# Main.net
KiCad netlist of a schematic drawn in Altium Designer
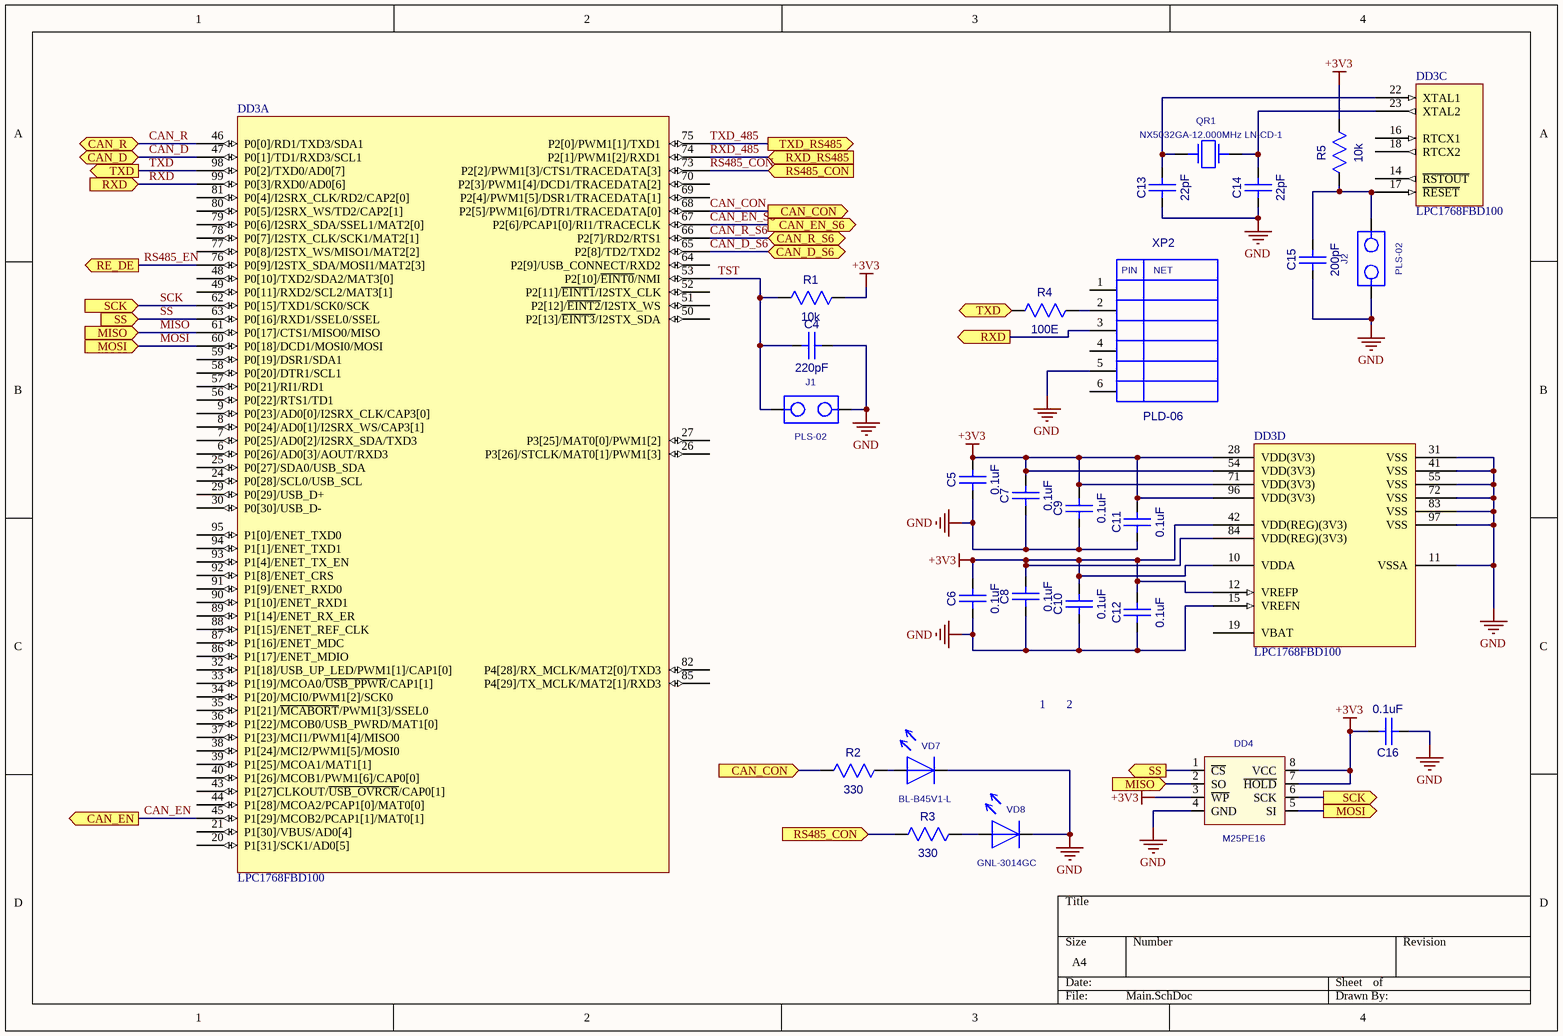
[diagram p0: Main.SchDoc]

(export (version "E")
  (design (tool "Eeschema 10.0.6"))
  (components
    (comp (ref "1")
      (value "REPER1.2")
      (footprint "REPER1.2")
      (libsource (lib "gprs_modem") (part "REPER1.2"))
    )
    (comp (ref "2")
      (value "REPER1.2")
      (footprint "REPER1.2")
      (libsource (lib "gprs_modem") (part "REPER1.2"))
    )
    (comp (ref "C4")
      (value "220pF")
      (footprint "CC0603-3M")
      (description "CC0603")
      (libsource (lib "gprs_modem") (part "CC0603"))
    )
    (comp (ref "C5")
      (value "0.1uF")
      (footprint "CC0603-3M")
      (description "CC0603")
      (libsource (lib "gprs_modem") (part "CC0603"))
    )
    (comp (ref "C6")
      (value "0.1uF")
      (footprint "CC0603-3M")
      (description "CC0603")
      (libsource (lib "gprs_modem") (part "CC0603"))
    )
    (comp (ref "C7")
      (value "0.1uF")
      (footprint "CC0603-3M")
      (description "CC0603")
      (libsource (lib "gprs_modem") (part "CC0603"))
    )
    (comp (ref "C8")
      (value "0.1uF")
      (footprint "CC0603-3M")
      (description "CC0603")
      (libsource (lib "gprs_modem") (part "CC0603"))
    )
    (comp (ref "C9")
      (value "0.1uF")
      (footprint "CC0603-3M")
      (description "CC0603")
      (libsource (lib "gprs_modem") (part "CC0603"))
    )
    (comp (ref "C10")
      (value "0.1uF")
      (footprint "CC0603-3M")
      (description "CC0603")
      (libsource (lib "gprs_modem") (part "CC0603"))
    )
    (comp (ref "C11")
      (value "0.1uF")
      (footprint "CC0603-3M")
      (description "CC0603")
      (libsource (lib "gprs_modem") (part "CC0603"))
    )
    (comp (ref "C12")
      (value "0.1uF")
      (footprint "CC0603-3M")
      (description "CC0603")
      (libsource (lib "gprs_modem") (part "CC0603"))
    )
    (comp (ref "C13")
      (value "22pF")
      (footprint "CC0603-3M")
      (description "CC0603")
      (libsource (lib "gprs_modem") (part "CC0603"))
    )
    (comp (ref "C14")
      (value "22pF")
      (footprint "CC0603-3M")
      (description "CC0603")
      (libsource (lib "gprs_modem") (part "CC0603"))
    )
    (comp (ref "C15")
      (value "200pF")
      (footprint "CC0603-3M")
      (description "CC0603")
      (libsource (lib "gprs_modem") (part "CC0603"))
    )
    (comp (ref "C16")
      (value "0.1uF")
      (footprint "CC0603-3M")
      (description "CC0603")
      (libsource (lib "") (part "CC0603_1"))
    )
    (comp (ref "DD3")
      (value "LPC1768FBD100")
      (footprint "TQFP-100")
      (description "Cortex -M3 32-Bit Microcontroller, 512KB Flash, 64KB RAM, 100-Lead LQFP")
      (libsource (lib "gprs_modem") (part "LPC1768FBD100"))
    )
    (comp (ref "DD4")
      (value "M25PE16")
      (footprint "EIAJ_SO8")
      (description "S25FL016A0LMFI01")
      (libsource (lib "gprs_modem") (part "S25FL016A0LMFI01"))
    )
    (comp (ref "J1") (value "PLS-02") (footprint "PLS-02") (libsource (lib "gprs_modem") (part "PLS-02")))
    (comp (ref "J2") (value "PLS-02") (footprint "PIN2W") (libsource (lib "gprs_modem") (part "PLS-02")))
    (comp (ref "QR1")
      (value "NX5032GA-12.000MHz LN-CD-1")
      (footprint "AC5032_2")
      (description "AC5032/2")
      (libsource (lib "gprs_modem") (part "AC5032_2"))
    )
    (comp (ref "R1")
      (value "10k")
      (footprint "RC0603-3M")
      (description "RC0603")
      (libsource (lib "gprs_modem") (part "RC0603"))
    )
    (comp (ref "R2")
      (value "330")
      (footprint "RC0603-3M")
      (description "RC0603")
      (libsource (lib "gprs_modem") (part "RC0603"))
    )
    (comp (ref "R3")
      (value "330")
      (footprint "RC0603-3M")
      (description "RC0603")
      (libsource (lib "gprs_modem") (part "RC0603"))
    )
    (comp (ref "R4")
      (value "100E")
      (footprint "RC0603-3M")
      (description "RC0603")
      (libsource (lib "gprs_modem") (part "RC0603"))
    )
    (comp (ref "R5")
      (value "10k")
      (footprint "RC0603-3M")
      (description "RC0603")
      (libsource (lib "gprs_modem") (part "RC0603"))
    )
    (comp (ref "VD7")
      (value "BL-B45V1-L")
      (footprint "LED3")
      (description "LED_3")
      (libsource (lib "gprs_modem") (part "LED_3"))
    )
    (comp (ref "VD8")
      (value "GNL-3014GC")
      (footprint "LED3")
      (description "LED_3")
      (libsource (lib "gprs_modem") (part "LED_3"))
    )
    (comp (ref "XP2")
      (value "PLD-06")
      (footprint "PLD-06")
      (description "PLD06")
      (libsource (lib "gprs_modem") (part "PLD-06"))
    )
  )
  (nets
    (net (code "1") (name "+3V3") (class "Default")
      (node (ref "C10") (pin "2") (pinfunction "B_2") (pintype "passive"))
      (node (ref "C11") (pin "2") (pinfunction "B_2") (pintype "passive"))
      (node (ref "C12") (pin "2") (pinfunction "B_2") (pintype "passive"))
      (node (ref "C16") (pin "2") (pinfunction "B_2") (pintype "passive"))
      (node (ref "C5") (pin "2") (pinfunction "B_2") (pintype "passive"))
      (node (ref "C6") (pin "2") (pinfunction "B_2") (pintype "passive"))
      (node (ref "C7") (pin "2") (pinfunction "B_2") (pintype "passive"))
      (node (ref "C8") (pin "2") (pinfunction "B_2") (pintype "passive"))
      (node (ref "C9") (pin "2") (pinfunction "B_2") (pintype "passive"))
      (node (ref "DD3") (pin "10") (pinfunction "VDDA_10") (pintype "power_in"))
      (node (ref "DD3") (pin "12") (pinfunction "VREFP_12") (pintype "input"))
      (node (ref "DD3") (pin "28") (pinfunction "VDD(3V3)_28") (pintype "power_in"))
      (node (ref "DD3") (pin "42") (pinfunction "VDD(REG)(3V3)_42") (pintype "power_in"))
      (node (ref "DD3") (pin "54") (pinfunction "VDD(3V3)_54") (pintype "power_in"))
      (node (ref "DD3") (pin "71") (pinfunction "VDD(3V3)_71") (pintype "power_in"))
      (node (ref "DD3") (pin "84") (pinfunction "VDD(REG)(3V3)_84") (pintype "power_in"))
      (node (ref "DD3") (pin "96") (pinfunction "VDD(3V3)_96") (pintype "power_in"))
      (node (ref "DD4") (pin "3") (pinfunction "~{WP}_3") (pintype "passive"))
      (node (ref "DD4") (pin "7") (pinfunction "~{HOLD}_7") (pintype "passive"))
      (node (ref "DD4") (pin "8") (pinfunction "VCC_8") (pintype "passive"))
      (node (ref "R1") (pin "2") (pinfunction "B_2") (pintype "passive"))
      (node (ref "R5") (pin "2") (pinfunction "B_2") (pintype "passive"))
    )
    (net (code "2") (name "/CAN_CON") (class "Default")
      (node (ref "DD3") (pin "68") (pinfunction "P2[5]/PWM1[6]/DTR1/TRACEDATA[0]_68") (pintype "bidirectional"))
      (node (ref "R2") (pin "1") (pinfunction "A_1") (pintype "passive"))
    )
    (net (code "3") (name "/CAN_D") (class "Default")
      (node (ref "DD3") (pin "47") (pinfunction "P0[1]/TD1/RXD3/SCL1_47") (pintype "bidirectional"))
    )
    (net (code "4") (name "/CAN_D_S6") (class "Default")
      (node (ref "DD3") (pin "65") (pinfunction "P2[8]/TD2/TXD2_65") (pintype "bidirectional"))
    )
    (net (code "5") (name "/CAN_EN") (class "Default")
      (node (ref "DD3") (pin "45") (pinfunction "P1[29]/MCOB2/PCAP1[1]/MAT0[1]_45") (pintype "bidirectional"))
    )
    (net (code "6") (name "/CAN_EN_S6") (class "Default")
      (node (ref "DD3") (pin "67") (pinfunction "P2[6]/PCAP1[0]/RI1/TRACECLK_67") (pintype "bidirectional"))
    )
    (net (code "7") (name "/CAN_R") (class "Default")
      (node (ref "DD3") (pin "46") (pinfunction "P0[0]/RD1/TXD3/SDA1_46") (pintype "bidirectional"))
    )
    (net (code "8") (name "/CAN_R_S6") (class "Default")
      (node (ref "DD3") (pin "66") (pinfunction "P2[7]/RD2/RTS1_66") (pintype "bidirectional"))
    )
    (net (code "9") (name "/MISO") (class "Default")
      (node (ref "DD3") (pin "61") (pinfunction "P0[17]/CTS1/MISO0/MISO_61") (pintype "bidirectional"))
      (node (ref "DD4") (pin "2") (pinfunction "SO_2") (pintype "passive"))
    )
    (net (code "10") (name "/MOSI") (class "Default")
      (node (ref "DD3") (pin "60") (pinfunction "P0[18]/DCD1/MOSI0/MOSI_60") (pintype "bidirectional"))
      (node (ref "DD4") (pin "5") (pinfunction "SI_5") (pintype "passive"))
    )
    (net (code "11") (name "/RS485_CON") (class "Default")
      (node (ref "DD3") (pin "73") (pinfunction "P2[2]/PWM1[3]/CTS1/TRACEDATA[3]_73") (pintype "bidirectional"))
      (node (ref "R3") (pin "1") (pinfunction "A_1") (pintype "passive"))
    )
    (net (code "12") (name "/RS485_EN") (class "Default")
      (node (ref "DD3") (pin "76") (pinfunction "P0[9]/I2STX_SDA/MOSI1/MAT2[3]_76") (pintype "bidirectional"))
    )
    (net (code "13") (name "/RXD") (class "Default")
      (node (ref "DD3") (pin "99") (pinfunction "P0[3]/RXD0/AD0[6]_99") (pintype "bidirectional"))
      (node (ref "XP2") (pin "3") (pinfunction "3_3") (pintype "passive"))
    )
    (net (code "14") (name "/RXD_485") (class "Default")
      (node (ref "DD3") (pin "74") (pinfunction "P2[1]/PWM1[2]/RXD1_74") (pintype "bidirectional"))
    )
    (net (code "15") (name "/SCK") (class "Default")
      (node (ref "DD3") (pin "62") (pinfunction "P0[15]/TXD1/SCK0/SCK_62") (pintype "bidirectional"))
      (node (ref "DD4") (pin "6") (pinfunction "SCK_6") (pintype "passive"))
    )
    (net (code "16") (name "/SS") (class "Default")
      (node (ref "DD3") (pin "63") (pinfunction "P0[16]/RXD1/SSEL0/SSEL_63") (pintype "bidirectional"))
      (node (ref "DD4") (pin "1") (pinfunction "~{CS}_1") (pintype "passive"))
    )
    (net (code "17") (name "/TST") (class "Default")
      (node (ref "C4") (pin "1") (pinfunction "A_1") (pintype "passive"))
      (node (ref "DD3") (pin "53") (pinfunction "P2[10]/~{EINT0}/NMI_53") (pintype "bidirectional"))
      (node (ref "J1") (pin "1") (pintype "passive"))
      (node (ref "R1") (pin "1") (pinfunction "A_1") (pintype "passive"))
    )
    (net (code "18") (name "/TXD") (class "Default")
      (node (ref "DD3") (pin "98") (pinfunction "P0[2]/TXD0/AD0[7]_98") (pintype "bidirectional"))
      (node (ref "R4") (pin "1") (pinfunction "A_1") (pintype "passive"))
    )
    (net (code "19") (name "/TXD_485") (class "Default")
      (node (ref "DD3") (pin "75") (pinfunction "P2[0]/PWM1[1]/TXD1_75") (pintype "bidirectional"))
    )
    (net (code "20") (name "GND") (class "Default")
      (node (ref "C10") (pin "1") (pinfunction "A_1") (pintype "passive"))
      (node (ref "C11") (pin "1") (pinfunction "A_1") (pintype "passive"))
      (node (ref "C12") (pin "1") (pinfunction "A_1") (pintype "passive"))
      (node (ref "C13") (pin "1") (pinfunction "A_1") (pintype "passive"))
      (node (ref "C14") (pin "1") (pinfunction "A_1") (pintype "passive"))
      (node (ref "C15") (pin "1") (pinfunction "A_1") (pintype "passive"))
      (node (ref "C16") (pin "1") (pinfunction "A_1") (pintype "passive"))
      (node (ref "C4") (pin "2") (pinfunction "B_2") (pintype "passive"))
      (node (ref "C5") (pin "1") (pinfunction "A_1") (pintype "passive"))
      (node (ref "C6") (pin "1") (pinfunction "A_1") (pintype "passive"))
      (node (ref "C7") (pin "1") (pinfunction "A_1") (pintype "passive"))
      (node (ref "C8") (pin "1") (pinfunction "A_1") (pintype "passive"))
      (node (ref "C9") (pin "1") (pinfunction "A_1") (pintype "passive"))
      (node (ref "DD3") (pin "11") (pinfunction "VSSA_11") (pintype "power_in"))
      (node (ref "DD3") (pin "15") (pinfunction "VREFN_15") (pintype "input"))
      (node (ref "DD3") (pin "31") (pinfunction "VSS_31") (pintype "power_in"))
      (node (ref "DD3") (pin "41") (pinfunction "VSS_41") (pintype "power_in"))
      (node (ref "DD3") (pin "55") (pinfunction "VSS_55") (pintype "power_in"))
      (node (ref "DD3") (pin "72") (pinfunction "VSS_72") (pintype "power_in"))
      (node (ref "DD3") (pin "83") (pinfunction "VSS_83") (pintype "power_in"))
      (node (ref "DD3") (pin "97") (pinfunction "VSS_97") (pintype "power_in"))
      (node (ref "DD4") (pin "4") (pinfunction "GND_4") (pintype "passive"))
      (node (ref "J1") (pin "2") (pintype "passive"))
      (node (ref "J2") (pin "1") (pintype "passive"))
      (node (ref "VD7") (pin "1") (pintype "passive"))
      (node (ref "VD8") (pin "1") (pintype "passive"))
      (node (ref "XP2") (pin "5") (pinfunction "5_5") (pintype "passive"))
    )
    (net (code "21") (name "Net-(C13-B)") (class "Default")
      (node (ref "C13") (pin "2") (pinfunction "B_2") (pintype "passive"))
      (node (ref "DD3") (pin "22") (pinfunction "XTAL1_22") (pintype "input"))
      (node (ref "QR1") (pin "1") (pintype "passive"))
    )
    (net (code "22") (name "Net-(C14-B)") (class "Default")
      (node (ref "C14") (pin "2") (pinfunction "B_2") (pintype "passive"))
      (node (ref "DD3") (pin "23") (pinfunction "XTAL2_23") (pintype "output"))
      (node (ref "QR1") (pin "2") (pintype "passive"))
    )
    (net (code "23") (name "Net-(C15-B)") (class "Default")
      (node (ref "C15") (pin "2") (pinfunction "B_2") (pintype "passive"))
      (node (ref "DD3") (pin "17") (pinfunction "~{RESET}_17") (pintype "input"))
      (node (ref "J2") (pin "2") (pintype "passive"))
      (node (ref "R5") (pin "1") (pinfunction "A_1") (pintype "passive"))
    )
    (net (code "24") (name "Net-(R2-B)") (class "Default")
      (node (ref "R2") (pin "2") (pinfunction "B_2") (pintype "passive"))
      (node (ref "VD7") (pin "2") (pintype "passive"))
    )
    (net (code "25") (name "Net-(R3-B)") (class "Default")
      (node (ref "R3") (pin "2") (pinfunction "B_2") (pintype "passive"))
      (node (ref "VD8") (pin "2") (pintype "passive"))
    )
    (net (code "26") (name "Net-(R4-B)") (class "Default")
      (node (ref "R4") (pin "2") (pinfunction "B_2") (pintype "passive"))
      (node (ref "XP2") (pin "2") (pinfunction "2_2") (pintype "passive"))
    )
    (net (code "27") (name "unconnected-(1-Pad1)") (class "Default")
      (node (ref "1") (pin "1") (pintype "passive"))
    )
    (net (code "28") (name "unconnected-(2-Pad1)") (class "Default")
      (node (ref "2") (pin "1") (pintype "passive"))
    )
    (net (code "29") (name "unconnected-(DD3A-P0[4]{slash}I2SRX_CLK{slash}RD2{slash}CAP2[0]-Pad81)") (class "Default")
      (node (ref "DD3") (pin "81") (pinfunction "P0[4]/I2SRX_CLK/RD2/CAP2[0]_81") (pintype "bidirectional"))
    )
    (net (code "30") (name "unconnected-(DD3A-P0[5]{slash}I2SRX_WS{slash}TD2{slash}CAP2[1]-Pad80)") (class "Default")
      (node (ref "DD3") (pin "80") (pinfunction "P0[5]/I2SRX_WS/TD2/CAP2[1]_80") (pintype "bidirectional"))
    )
    (net (code "31") (name "unconnected-(DD3A-P0[6]{slash}I2SRX_SDA{slash}SSEL1{slash}MAT2[0]-Pad79)") (class "Default")
      (node (ref "DD3") (pin "79") (pinfunction "P0[6]/I2SRX_SDA/SSEL1/MAT2[0]_79") (pintype "bidirectional"))
    )
    (net (code "32") (name "unconnected-(DD3A-P0[7]{slash}I2STX_CLK{slash}SCK1{slash}MAT2[1]-Pad78)") (class "Default")
      (node (ref "DD3") (pin "78") (pinfunction "P0[7]/I2STX_CLK/SCK1/MAT2[1]_78") (pintype "bidirectional"))
    )
    (net (code "33") (name "unconnected-(DD3A-P0[8]{slash}I2STX_WS{slash}MISO1{slash}MAT2[2]-Pad77)") (class "Default")
      (node (ref "DD3") (pin "77") (pinfunction "P0[8]/I2STX_WS/MISO1/MAT2[2]_77") (pintype "bidirectional"))
    )
    (net (code "34") (name "unconnected-(DD3A-P0[10]{slash}TXD2{slash}SDA2{slash}MAT3[0]-Pad48)") (class "Default")
      (node (ref "DD3") (pin "48") (pinfunction "P0[10]/TXD2/SDA2/MAT3[0]_48") (pintype "bidirectional"))
    )
    (net (code "35") (name "unconnected-(DD3A-P0[11]{slash}RXD2{slash}SCL2{slash}MAT3[1]-Pad49)") (class "Default")
      (node (ref "DD3") (pin "49") (pinfunction "P0[11]/RXD2/SCL2/MAT3[1]_49") (pintype "bidirectional"))
    )
    (net (code "36") (name "unconnected-(DD3A-P0[19]{slash}DSR1{slash}SDA1-Pad59)") (class "Default")
      (node (ref "DD3") (pin "59") (pinfunction "P0[19]/DSR1/SDA1_59") (pintype "bidirectional"))
    )
    (net (code "37") (name "unconnected-(DD3A-P0[20]{slash}DTR1{slash}SCL1-Pad58)") (class "Default")
      (node (ref "DD3") (pin "58") (pinfunction "P0[20]/DTR1/SCL1_58") (pintype "bidirectional"))
    )
    (net (code "38") (name "unconnected-(DD3A-P0[21]{slash}RI1{slash}RD1-Pad57)") (class "Default")
      (node (ref "DD3") (pin "57") (pinfunction "P0[21]/RI1/RD1_57") (pintype "bidirectional"))
    )
    (net (code "39") (name "unconnected-(DD3A-P0[22]{slash}RTS1{slash}TD1-Pad56)") (class "Default")
      (node (ref "DD3") (pin "56") (pinfunction "P0[22]/RTS1/TD1_56") (pintype "bidirectional"))
    )
    (net (code "40") (name "unconnected-(DD3A-P0[23]{slash}AD0[0]{slash}I2SRX_CLK{slash}CAP3[0]-Pad9)") (class "Default")
      (node (ref "DD3") (pin "9") (pinfunction "P0[23]/AD0[0]/I2SRX_CLK/CAP3[0]_9") (pintype "bidirectional"))
    )
    (net (code "41") (name "unconnected-(DD3A-P0[24]{slash}AD0[1]{slash}I2SRX_WS{slash}CAP3[1]-Pad8)") (class "Default")
      (node (ref "DD3") (pin "8") (pinfunction "P0[24]/AD0[1]/I2SRX_WS/CAP3[1]_8") (pintype "bidirectional"))
    )
    (net (code "42") (name "unconnected-(DD3A-P0[25]{slash}AD0[2]{slash}I2SRX_SDA{slash}TXD3-Pad7)") (class "Default")
      (node (ref "DD3") (pin "7") (pinfunction "P0[25]/AD0[2]/I2SRX_SDA/TXD3_7") (pintype "bidirectional"))
    )
    (net (code "43") (name "unconnected-(DD3A-P0[26]{slash}AD0[3]{slash}AOUT{slash}RXD3-Pad6)") (class "Default")
      (node (ref "DD3") (pin "6") (pinfunction "P0[26]/AD0[3]/AOUT/RXD3_6") (pintype "bidirectional"))
    )
    (net (code "44") (name "unconnected-(DD3A-P0[27]{slash}SDA0{slash}USB_SDA-Pad25)") (class "Default")
      (node (ref "DD3") (pin "25") (pinfunction "P0[27]/SDA0/USB_SDA_25") (pintype "bidirectional"))
    )
    (net (code "45") (name "unconnected-(DD3A-P0[28]{slash}SCL0{slash}USB_SCL-Pad24)") (class "Default")
      (node (ref "DD3") (pin "24") (pinfunction "P0[28]/SCL0/USB_SCL_24") (pintype "bidirectional"))
    )
    (net (code "46") (name "unconnected-(DD3A-P0[29]{slash}USB_D+-Pad29)") (class "Default")
      (node (ref "DD3") (pin "29") (pinfunction "P0[29]/USB_D+_29") (pintype "bidirectional"))
    )
    (net (code "47") (name "unconnected-(DD3A-P0[30]{slash}USB_D--Pad30)") (class "Default")
      (node (ref "DD3") (pin "30") (pinfunction "P0[30]/USB_D-_30") (pintype "bidirectional"))
    )
    (net (code "48") (name "unconnected-(DD3A-P1[0]{slash}ENET_TXD0-Pad95)") (class "Default")
      (node (ref "DD3") (pin "95") (pinfunction "P1[0]/ENET_TXD0_95") (pintype "bidirectional"))
    )
    (net (code "49") (name "unconnected-(DD3A-P1[1]{slash}ENET_TXD1-Pad94)") (class "Default")
      (node (ref "DD3") (pin "94") (pinfunction "P1[1]/ENET_TXD1_94") (pintype "bidirectional"))
    )
    (net (code "50") (name "unconnected-(DD3A-P1[4]{slash}ENET_TX_EN-Pad93)") (class "Default")
      (node (ref "DD3") (pin "93") (pinfunction "P1[4]/ENET_TX_EN_93") (pintype "bidirectional"))
    )
    (net (code "51") (name "unconnected-(DD3A-P1[8]{slash}ENET_CRS-Pad92)") (class "Default")
      (node (ref "DD3") (pin "92") (pinfunction "P1[8]/ENET_CRS_92") (pintype "bidirectional"))
    )
    (net (code "52") (name "unconnected-(DD3A-P1[9]{slash}ENET_RXD0-Pad91)") (class "Default")
      (node (ref "DD3") (pin "91") (pinfunction "P1[9]/ENET_RXD0_91") (pintype "bidirectional"))
    )
    (net (code "53") (name "unconnected-(DD3A-P1[10]{slash}ENET_RXD1-Pad90)") (class "Default")
      (node (ref "DD3") (pin "90") (pinfunction "P1[10]/ENET_RXD1_90") (pintype "bidirectional"))
    )
    (net (code "54") (name "unconnected-(DD3A-P1[14]{slash}ENET_RX_ER-Pad89)") (class "Default")
      (node (ref "DD3") (pin "89") (pinfunction "P1[14]/ENET_RX_ER_89") (pintype "bidirectional"))
    )
    (net (code "55") (name "unconnected-(DD3A-P1[15]{slash}ENET_REF_CLK-Pad88)") (class "Default")
      (node (ref "DD3") (pin "88") (pinfunction "P1[15]/ENET_REF_CLK_88") (pintype "bidirectional"))
    )
    (net (code "56") (name "unconnected-(DD3A-P1[16]{slash}ENET_MDC-Pad87)") (class "Default")
      (node (ref "DD3") (pin "87") (pinfunction "P1[16]/ENET_MDC_87") (pintype "bidirectional"))
    )
    (net (code "57") (name "unconnected-(DD3A-P1[17]{slash}ENET_MDIO-Pad86)") (class "Default")
      (node (ref "DD3") (pin "86") (pinfunction "P1[17]/ENET_MDIO_86") (pintype "bidirectional"))
    )
    (net (code "58") (name "unconnected-(DD3A-P1[18]{slash}USB_UP_LED{slash}PWM1[1]{slash}CAP1[0]-Pad32)") (class "Default")
      (node (ref "DD3") (pin "32") (pinfunction "P1[18]/USB_UP_LED/PWM1[1]/CAP1[0]_32") (pintype "bidirectional"))
    )
    (net (code "59") (name "unconnected-(DD3A-P1[19]{slash}MCOA0{slash}~{USB_PPWR}{slash}CAP1[1]-Pad33)") (class "Default")
      (node (ref "DD3") (pin "33") (pinfunction "P1[19]/MCOA0/~{USB_PPWR}/CAP1[1]_33") (pintype "bidirectional"))
    )
    (net (code "60") (name "unconnected-(DD3A-P1[20]{slash}MCI0{slash}PWM1[2]{slash}SCK0-Pad34)") (class "Default")
      (node (ref "DD3") (pin "34") (pinfunction "P1[20]/MCI0/PWM1[2]/SCK0_34") (pintype "bidirectional"))
    )
    (net (code "61") (name "unconnected-(DD3A-P1[21]{slash}~{MCABORT}{slash}PWM1[3]{slash}SSEL0-Pad35)") (class "Default")
      (node (ref "DD3") (pin "35") (pinfunction "P1[21]/~{MCABORT}/PWM1[3]/SSEL0_35") (pintype "bidirectional"))
    )
    (net (code "62") (name "unconnected-(DD3A-P1[22]{slash}MCOB0{slash}USB_PWRD{slash}MAT1[0]-Pad36)") (class "Default")
      (node (ref "DD3") (pin "36") (pinfunction "P1[22]/MCOB0/USB_PWRD/MAT1[0]_36") (pintype "bidirectional"))
    )
    (net (code "63") (name "unconnected-(DD3A-P1[23]{slash}MCI1{slash}PWM1[4]{slash}MISO0-Pad37)") (class "Default")
      (node (ref "DD3") (pin "37") (pinfunction "P1[23]/MCI1/PWM1[4]/MISO0_37") (pintype "bidirectional"))
    )
    (net (code "64") (name "unconnected-(DD3A-P1[24]{slash}MCI2{slash}PWM1[5]{slash}MOSI0-Pad38)") (class "Default")
      (node (ref "DD3") (pin "38") (pinfunction "P1[24]/MCI2/PWM1[5]/MOSI0_38") (pintype "bidirectional"))
    )
    (net (code "65") (name "unconnected-(DD3A-P1[25]{slash}MCOA1{slash}MAT1[1]-Pad39)") (class "Default")
      (node (ref "DD3") (pin "39") (pinfunction "P1[25]/MCOA1/MAT1[1]_39") (pintype "bidirectional"))
    )
    (net (code "66") (name "unconnected-(DD3A-P1[26]{slash}MCOB1{slash}PWM1[6]{slash}CAP0[0]-Pad40)") (class "Default")
      (node (ref "DD3") (pin "40") (pinfunction "P1[26]/MCOB1/PWM1[6]/CAP0[0]_40") (pintype "bidirectional"))
    )
    (net (code "67") (name "unconnected-(DD3A-P1[27]CLKOUT{slash}~{USB_OVRCR}{slash}CAP0[1]-Pad43)") (class "Default")
      (node (ref "DD3") (pin "43") (pinfunction "P1[27]CLKOUT/~{USB_OVRCR}/CAP0[1]_43") (pintype "bidirectional"))
    )
    (net (code "68") (name "unconnected-(DD3A-P1[28]{slash}MCOA2{slash}PCAP1[0]{slash}MAT0[0]-Pad44)") (class "Default")
      (node (ref "DD3") (pin "44") (pinfunction "P1[28]/MCOA2/PCAP1[0]/MAT0[0]_44") (pintype "bidirectional"))
    )
    (net (code "69") (name "unconnected-(DD3A-P1[30]{slash}VBUS{slash}AD0[4]-Pad21)") (class "Default")
      (node (ref "DD3") (pin "21") (pinfunction "P1[30]/VBUS/AD0[4]_21") (pintype "bidirectional"))
    )
    (net (code "70") (name "unconnected-(DD3A-P1[31]{slash}SCK1{slash}AD0[5]-Pad20)") (class "Default")
      (node (ref "DD3") (pin "20") (pinfunction "P1[31]/SCK1/AD0[5]_20") (pintype "bidirectional"))
    )
    (net (code "71") (name "unconnected-(DD3A-P2[3]{slash}PWM1[4]{slash}DCD1{slash}TRACEDATA[2]-Pad70)") (class "Default")
      (node (ref "DD3") (pin "70") (pinfunction "P2[3]/PWM1[4]/DCD1/TRACEDATA[2]_70") (pintype "bidirectional"))
    )
    (net (code "72") (name "unconnected-(DD3A-P2[4]{slash}PWM1[5]{slash}DSR1{slash}TRACEDATA[1]-Pad69)") (class "Default")
      (node (ref "DD3") (pin "69") (pinfunction "P2[4]/PWM1[5]/DSR1/TRACEDATA[1]_69") (pintype "bidirectional"))
    )
    (net (code "73") (name "unconnected-(DD3A-P2[9]{slash}USB_CONNECT{slash}RXD2-Pad64)") (class "Default")
      (node (ref "DD3") (pin "64") (pinfunction "P2[9]/USB_CONNECT/RXD2_64") (pintype "bidirectional"))
    )
    (net (code "74") (name "unconnected-(DD3A-P2[11]{slash}~{EINT1}{slash}I2STX_CLK-Pad52)") (class "Default")
      (node (ref "DD3") (pin "52") (pinfunction "P2[11]/~{EINT1}/I2STX_CLK_52") (pintype "bidirectional"))
    )
    (net (code "75") (name "unconnected-(DD3A-P2[12]{slash}~{EINT2}{slash}I2STX_WS-Pad51)") (class "Default")
      (node (ref "DD3") (pin "51") (pinfunction "P2[12]/~{EINT2}/I2STX_WS_51") (pintype "bidirectional"))
    )
    (net (code "76") (name "unconnected-(DD3A-P2[13]{slash}~{EINT3}{slash}I2STX_SDA-Pad50)") (class "Default")
      (node (ref "DD3") (pin "50") (pinfunction "P2[13]/~{EINT3}/I2STX_SDA_50") (pintype "bidirectional"))
    )
    (net (code "77") (name "unconnected-(DD3A-P3[25]{slash}MAT0[0]{slash}PWM1[2]-Pad27)") (class "Default")
      (node (ref "DD3") (pin "27") (pinfunction "P3[25]/MAT0[0]/PWM1[2]_27") (pintype "bidirectional"))
    )
    (net (code "78") (name "unconnected-(DD3A-P3[26]{slash}STCLK{slash}MAT0[1]{slash}PWM1[3]-Pad26)") (class "Default")
      (node (ref "DD3") (pin "26") (pinfunction "P3[26]/STCLK/MAT0[1]/PWM1[3]_26") (pintype "bidirectional"))
    )
    (net (code "79") (name "unconnected-(DD3A-P4[28]{slash}RX_MCLK{slash}MAT2[0]{slash}TXD3-Pad82)") (class "Default")
      (node (ref "DD3") (pin "82") (pinfunction "P4[28]/RX_MCLK/MAT2[0]/TXD3_82") (pintype "bidirectional"))
    )
    (net (code "80") (name "unconnected-(DD3A-P4[29]{slash}TX_MCLK{slash}MAT2[1]{slash}RXD3-Pad85)") (class "Default")
      (node (ref "DD3") (pin "85") (pinfunction "P4[29]/TX_MCLK/MAT2[1]/RXD3_85") (pintype "bidirectional"))
    )
    (net (code "81") (name "unconnected-(DD3C-RTCX1-Pad16)") (class "Default")
      (node (ref "DD3") (pin "16") (pinfunction "RTCX1_16") (pintype "input"))
    )
    (net (code "82") (name "unconnected-(DD3C-RTCX2-Pad18)") (class "Default")
      (node (ref "DD3") (pin "18") (pinfunction "RTCX2_18") (pintype "output"))
    )
    (net (code "83") (name "unconnected-(DD3C-~{RSTOUT}-Pad14)") (class "Default")
      (node (ref "DD3") (pin "14") (pinfunction "~{RSTOUT}_14") (pintype "output"))
    )
    (net (code "84") (name "unconnected-(DD3D-VBAT-Pad19)") (class "Default")
      (node (ref "DD3") (pin "19") (pinfunction "VBAT_19") (pintype "power_in"))
    )
    (net (code "85") (name "unconnected-(XP2-Pad1)") (class "Default")
      (node (ref "XP2") (pin "1") (pinfunction "1_1") (pintype "passive"))
    )
    (net (code "86") (name "unconnected-(XP2-Pad4)") (class "Default")
      (node (ref "XP2") (pin "4") (pinfunction "4_4") (pintype "passive"))
    )
    (net (code "87") (name "unconnected-(XP2-Pad6)") (class "Default")
      (node (ref "XP2") (pin "6") (pinfunction "6_6") (pintype "passive"))
    )
  )
)
